# untitled.net
KiCad netlist of a schematic drawn in EAGLE
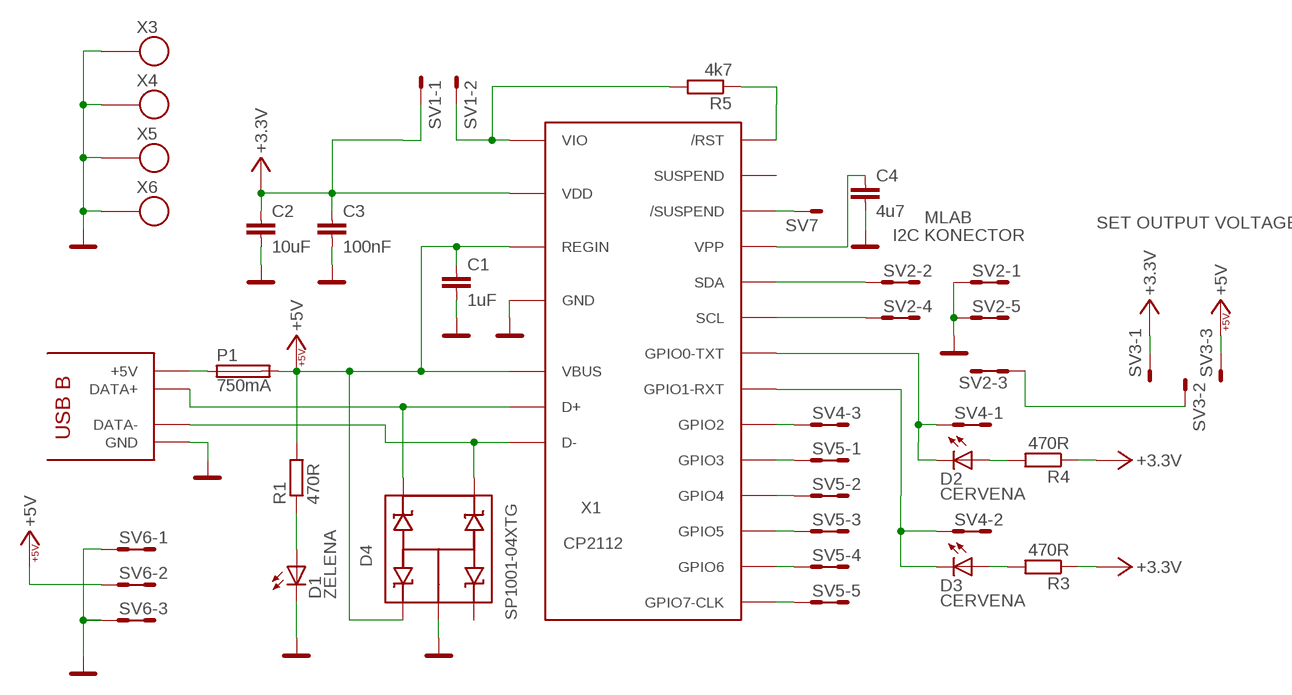
[diagram p0: schematic, sheet 1]

(export (version "E")
  (design (tool "Eeschema 10.0.6"))
  (components
    (comp (ref "C1")
      (value "1uF")
      (footprint "eagle-import:C0805")
      (libsource (lib "eagle-import") (part "C0805"))
    )
    (comp (ref "C2")
      (value "10uF")
      (footprint "eagle-import:C0805")
      (libsource (lib "eagle-import") (part "C0805"))
    )
    (comp (ref "C3")
      (value "100nF")
      (footprint "eagle-import:C0805")
      (libsource (lib "eagle-import") (part "C0805"))
    )
    (comp (ref "C4")
      (value "4u7")
      (footprint "eagle-import:C0805")
      (libsource (lib "eagle-import") (part "C0805"))
    )
    (comp (ref "D1")
      (value "ZELENA")
      (footprint "eagle-import:1206_2")
      (libsource (lib "eagle-import") (part "LED1206_2"))
    )
    (comp (ref "D2")
      (value "CERVENA")
      (footprint "eagle-import:1206_2")
      (libsource (lib "eagle-import") (part "LED1206_2"))
    )
    (comp (ref "D3")
      (value "CERVENA")
      (footprint "eagle-import:1206_2")
      (libsource (lib "eagle-import") (part "LED1206_2"))
    )
    (comp (ref "D4")
      (value "SP1001-04XTG")
      (footprint "eagle-import:SOT553")
      (libsource (lib "eagle-import") (part "CP2112"))
    )
    (comp (ref "P1")
      (value "750mA")
      (footprint "eagle-import:1812")
      (libsource (lib "eagle-import") (part "POJISTKA_1812"))
    )
    (comp (ref "R1")
      (value "470R")
      (footprint "eagle-import:0805")
      (libsource (lib "eagle-import") (part "R0805"))
    )
    (comp (ref "R3")
      (value "470R")
      (footprint "eagle-import:0805")
      (libsource (lib "eagle-import") (part "R0805"))
    )
    (comp (ref "R4")
      (value "470R")
      (footprint "eagle-import:0805")
      (libsource (lib "eagle-import") (part "R0805"))
    )
    (comp (ref "R5")
      (value "4k7")
      (footprint "eagle-import:0805")
      (libsource (lib "eagle-import") (part "R0805"))
    )
    (comp (ref "SV1")
      (value "MA02-1")
      (footprint "eagle-import:MA02-1")
      (libsource (lib "eagle-import") (part "MA02-1"))
    )
    (comp (ref "SV2")
      (value "MA05-2")
      (footprint "eagle-import:MA05-2")
      (libsource (lib "eagle-import") (part "MA05-2"))
    )
    (comp (ref "SV3")
      (value "MA03-1")
      (footprint "eagle-import:MA03-1")
      (libsource (lib "eagle-import") (part "MA03-1"))
    )
    (comp (ref "SV4")
      (value "MA03-2")
      (footprint "eagle-import:MA03-2")
      (libsource (lib "eagle-import") (part "MA03-2"))
    )
    (comp (ref "SV5")
      (value "MA05-2")
      (footprint "eagle-import:MA05-2")
      (libsource (lib "eagle-import") (part "MA05-2"))
    )
    (comp (ref "SV6")
      (value "MA03-2")
      (footprint "eagle-import:MA03-2")
      (libsource (lib "eagle-import") (part "MA03-2"))
    )
    (comp (ref "SV7")
      (value "MA01-1")
      (footprint "eagle-import:MA01-1")
      (libsource (lib "eagle-import") (part "MA01-1"))
    )
    (comp (ref "X1")
      (value "CP2112")
      (footprint "eagle-import:QFN-24")
      (libsource (lib "eagle-import") (part "moje_io_CP2112"))
    )
    (comp (ref "X2")
      (value "USB_B")
      (footprint "eagle-import:USB_B")
      (libsource (lib "eagle-import") (part "USB_B"))
    )
    (comp (ref "X3")
      (value "SROUB3M")
      (footprint "eagle-import:SROUB3M")
      (libsource (lib "eagle-import") (part "SROUB3M"))
    )
    (comp (ref "X4")
      (value "SROUB3M")
      (footprint "eagle-import:SROUB3M")
      (libsource (lib "eagle-import") (part "SROUB3M"))
    )
    (comp (ref "X5")
      (value "SROUB3M")
      (footprint "eagle-import:SROUB3M")
      (libsource (lib "eagle-import") (part "SROUB3M"))
    )
    (comp (ref "X6")
      (value "SROUB3M")
      (footprint "eagle-import:SROUB3M")
      (libsource (lib "eagle-import") (part "SROUB3M"))
    )
  )
  (nets
    (net (code "1") (name "+3.3V") (class "Default")
      (node (ref "C2") (pin "1") (pinfunction "1_1") (pintype "passive"))
      (node (ref "C3") (pin "1") (pinfunction "1_1") (pintype "passive"))
      (node (ref "R3") (pin "1") (pinfunction "1_1") (pintype "passive"))
      (node (ref "R4") (pin "1") (pinfunction "1_1") (pintype "passive"))
      (node (ref "SV1") (pin "1") (pinfunction "P$1_1") (pintype "passive"))
      (node (ref "SV3") (pin "1") (pinfunction "P$1_1") (pintype "passive"))
      (node (ref "X1") (pin "P$6") (pinfunction "VDD_P$6") (pintype "bidirectional"))
    )
    (net (code "2") (name "+5V") (class "Default")
      (node (ref "C1") (pin "1") (pinfunction "1_1") (pintype "passive"))
      (node (ref "D4") (pin "1") (pinfunction "P$1_1") (pintype "passive"))
      (node (ref "P1") (pin "2") (pinfunction "2_2") (pintype "passive"))
      (node (ref "R1") (pin "2") (pinfunction "2_2") (pintype "passive"))
      (node (ref "SV3") (pin "3") (pinfunction "P$1_3") (pintype "passive"))
      (node (ref "SV6") (pin "3") (pinfunction "K_3") (pintype "passive"))
      (node (ref "SV6") (pin "4") (pinfunction "K_4") (pintype "passive"))
      (node (ref "X1") (pin "P$7") (pinfunction "REGIN_P$7") (pintype "bidirectional"))
      (node (ref "X1") (pin "P$8") (pinfunction "VBUS_P$8") (pintype "bidirectional"))
    )
    (net (code "3") (name "GND") (class "Default")
      (node (ref "C1") (pin "2") (pinfunction "2_2") (pintype "passive"))
      (node (ref "C2") (pin "2") (pinfunction "2_2") (pintype "passive"))
      (node (ref "C3") (pin "2") (pinfunction "2_2") (pintype "passive"))
      (node (ref "C4") (pin "2") (pinfunction "2_2") (pintype "passive"))
      (node (ref "D1") (pin "K") (pinfunction "C_K") (pintype "passive"))
      (node (ref "D4") (pin "2") (pinfunction "P$2_2") (pintype "passive"))
      (node (ref "SV2") (pin "1") (pinfunction "K_1") (pintype "passive"))
      (node (ref "SV2") (pin "10") (pinfunction "K_10") (pintype "passive"))
      (node (ref "SV2") (pin "2") (pinfunction "K_2") (pintype "passive"))
      (node (ref "SV2") (pin "9") (pinfunction "K_9") (pintype "passive"))
      (node (ref "SV6") (pin "1") (pinfunction "K_1") (pintype "passive"))
      (node (ref "SV6") (pin "2") (pinfunction "K_2") (pintype "passive"))
      (node (ref "SV6") (pin "5") (pinfunction "K_5") (pintype "passive"))
      (node (ref "SV6") (pin "6") (pinfunction "K_6") (pintype "passive"))
      (node (ref "X1") (pin "P$2") (pinfunction "GND_P$2") (pintype "bidirectional"))
      (node (ref "X1") (pin "P$25") (pinfunction "GND_P$25") (pintype "bidirectional"))
      (node (ref "X2") (pin "4") (pinfunction "GND_4") (pintype "bidirectional"))
      (node (ref "X2") (pin "GND") (pinfunction "GND_GND") (pintype "bidirectional"))
      (node (ref "X2") (pin "GND2") (pinfunction "GND_GND2") (pintype "bidirectional"))
      (node (ref "X3") (pin "P$1") (pinfunction "P$1_P$1") (pintype "bidirectional"))
      (node (ref "X4") (pin "P$1") (pinfunction "P$1_P$1") (pintype "bidirectional"))
      (node (ref "X5") (pin "P$1") (pinfunction "P$1_P$1") (pintype "bidirectional"))
      (node (ref "X6") (pin "P$1") (pinfunction "P$1_P$1") (pintype "bidirectional"))
    )
    (net (code "4") (name "Net-(D1-PadA)") (class "Default")
      (node (ref "D1") (pin "A") (pinfunction "A_A") (pintype "passive"))
      (node (ref "R1") (pin "1") (pinfunction "1_1") (pintype "passive"))
    )
    (net (code "5") (name "Net-(D2-C)") (class "Default")
      (node (ref "D2") (pin "K") (pinfunction "C_K") (pintype "passive"))
      (node (ref "SV4") (pin "1") (pinfunction "K_1") (pintype "passive"))
      (node (ref "SV4") (pin "2") (pinfunction "K_2") (pintype "passive"))
      (node (ref "X1") (pin "P$23") (pinfunction "GPIO0-TXT_P$23") (pintype "bidirectional"))
    )
    (net (code "6") (name "Net-(D2-PadA)") (class "Default")
      (node (ref "D2") (pin "A") (pinfunction "A_A") (pintype "passive"))
      (node (ref "R4") (pin "2") (pinfunction "2_2") (pintype "passive"))
    )
    (net (code "7") (name "Net-(D3-C)") (class "Default")
      (node (ref "D3") (pin "K") (pinfunction "C_K") (pintype "passive"))
      (node (ref "SV4") (pin "3") (pinfunction "K_3") (pintype "passive"))
      (node (ref "SV4") (pin "4") (pinfunction "K_4") (pintype "passive"))
      (node (ref "X1") (pin "P$22") (pinfunction "GPIO1-RXT_P$22") (pintype "bidirectional"))
    )
    (net (code "8") (name "Net-(D3-PadA)") (class "Default")
      (node (ref "D3") (pin "A") (pinfunction "A_A") (pintype "passive"))
      (node (ref "R3") (pin "2") (pinfunction "2_2") (pintype "passive"))
    )
    (net (code "9") (name "Net-(D4-P$4)") (class "Default")
      (node (ref "D4") (pin "4") (pinfunction "P$4_4") (pintype "passive"))
      (node (ref "X1") (pin "P$4") (pinfunction "D-_P$4") (pintype "bidirectional"))
      (node (ref "X2") (pin "2") (pinfunction "DATA-_2") (pintype "bidirectional"))
    )
    (net (code "10") (name "Net-(D4-P$5)") (class "Default")
      (node (ref "D4") (pin "5") (pinfunction "P$5_5") (pintype "passive"))
      (node (ref "X1") (pin "P$3") (pinfunction "D+_P$3") (pintype "bidirectional"))
      (node (ref "X2") (pin "3") (pinfunction "DATA+_3") (pintype "bidirectional"))
    )
    (net (code "11") (name "Net-(SV1B-P$1)") (class "Default")
      (node (ref "R5") (pin "2") (pinfunction "2_2") (pintype "passive"))
      (node (ref "SV1") (pin "2") (pinfunction "P$1_2") (pintype "passive"))
      (node (ref "X1") (pin "P$5") (pinfunction "VIO_P$5") (pintype "bidirectional"))
    )
    (net (code "12") (name "Net-(SV3B-P$1)") (class "Default")
      (node (ref "SV2") (pin "5") (pinfunction "K_5") (pintype "passive"))
      (node (ref "SV2") (pin "6") (pinfunction "K_6") (pintype "passive"))
      (node (ref "SV3") (pin "2") (pinfunction "P$1_2") (pintype "passive"))
    )
    (net (code "13") (name "Net-(SV7-P$1)") (class "Default")
      (node (ref "SV7") (pin "1") (pinfunction "P$1_1") (pintype "passive"))
      (node (ref "X1") (pin "P$17") (pinfunction "/SUSPEND_P$17") (pintype "bidirectional"))
    )
    (net (code "14") (name "Net-(X1-GPIO2)") (class "Default")
      (node (ref "SV4") (pin "5") (pinfunction "K_5") (pintype "passive"))
      (node (ref "SV4") (pin "6") (pinfunction "K_6") (pintype "passive"))
      (node (ref "X1") (pin "P$21") (pinfunction "GPIO2_P$21") (pintype "bidirectional"))
    )
    (net (code "15") (name "Net-(X1-GPIO3)") (class "Default")
      (node (ref "SV5") (pin "1") (pinfunction "K_1") (pintype "passive"))
      (node (ref "SV5") (pin "2") (pinfunction "K_2") (pintype "passive"))
      (node (ref "X1") (pin "P$20") (pinfunction "GPIO3_P$20") (pintype "bidirectional"))
    )
    (net (code "16") (name "Net-(X1-GPIO4)") (class "Default")
      (node (ref "SV5") (pin "3") (pinfunction "K_3") (pintype "passive"))
      (node (ref "SV5") (pin "4") (pinfunction "K_4") (pintype "passive"))
      (node (ref "X1") (pin "P$15") (pinfunction "GPIO4_P$15") (pintype "bidirectional"))
    )
    (net (code "17") (name "Net-(X1-GPIO5)") (class "Default")
      (node (ref "SV5") (pin "5") (pinfunction "K_5") (pintype "passive"))
      (node (ref "SV5") (pin "6") (pinfunction "K_6") (pintype "passive"))
      (node (ref "X1") (pin "P$14") (pinfunction "GPIO5_P$14") (pintype "bidirectional"))
    )
    (net (code "18") (name "Net-(X1-GPIO6)") (class "Default")
      (node (ref "SV5") (pin "7") (pinfunction "K_7") (pintype "passive"))
      (node (ref "SV5") (pin "8") (pinfunction "K_8") (pintype "passive"))
      (node (ref "X1") (pin "P$13") (pinfunction "GPIO6_P$13") (pintype "bidirectional"))
    )
    (net (code "19") (name "Net-(X1-GPIO7-CLK)") (class "Default")
      (node (ref "SV5") (pin "10") (pinfunction "K_10") (pintype "passive"))
      (node (ref "SV5") (pin "9") (pinfunction "K_9") (pintype "passive"))
      (node (ref "X1") (pin "P$12") (pinfunction "GPIO7-CLK_P$12") (pintype "bidirectional"))
    )
    (net (code "20") (name "Net-(X1-SCL)") (class "Default")
      (node (ref "SV2") (pin "7") (pinfunction "K_7") (pintype "passive"))
      (node (ref "SV2") (pin "8") (pinfunction "K_8") (pintype "passive"))
      (node (ref "X1") (pin "P$24") (pinfunction "SCL_P$24") (pintype "bidirectional"))
    )
    (net (code "21") (name "Net-(X1-SDA)") (class "Default")
      (node (ref "SV2") (pin "3") (pinfunction "K_3") (pintype "passive"))
      (node (ref "SV2") (pin "4") (pinfunction "K_4") (pintype "passive"))
      (node (ref "X1") (pin "P$1") (pinfunction "SDA_P$1") (pintype "bidirectional"))
    )
    (net (code "22") (name "Net-(X1-VPP)") (class "Default")
      (node (ref "C4") (pin "1") (pinfunction "1_1") (pintype "passive"))
      (node (ref "X1") (pin "P$16") (pinfunction "VPP_P$16") (pintype "bidirectional"))
    )
    (net (code "23") (name "Net-(X1-{slash}RST)") (class "Default")
      (node (ref "R5") (pin "1") (pinfunction "1_1") (pintype "passive"))
      (node (ref "X1") (pin "P$9") (pinfunction "/RST_P$9") (pintype "bidirectional"))
    )
    (net (code "24") (name "Net-(X2-+5V)") (class "Default")
      (node (ref "P1") (pin "1") (pinfunction "1_1") (pintype "passive"))
      (node (ref "X2") (pin "1") (pinfunction "+5V_1") (pintype "bidirectional"))
    )
    (net (code "25") (name "unconnected-(D4-P$3-Pad3)") (class "Default")
      (node (ref "D4") (pin "3") (pinfunction "P$3_3") (pintype "passive"))
    )
    (net (code "26") (name "unconnected-(X1-SUSPEND-PadP$11)") (class "Default")
      (node (ref "X1") (pin "P$11") (pinfunction "SUSPEND_P$11") (pintype "bidirectional"))
    )
  )
)
